# BMS_Interface.net
KiCad netlist of a schematic drawn in Altium Designer
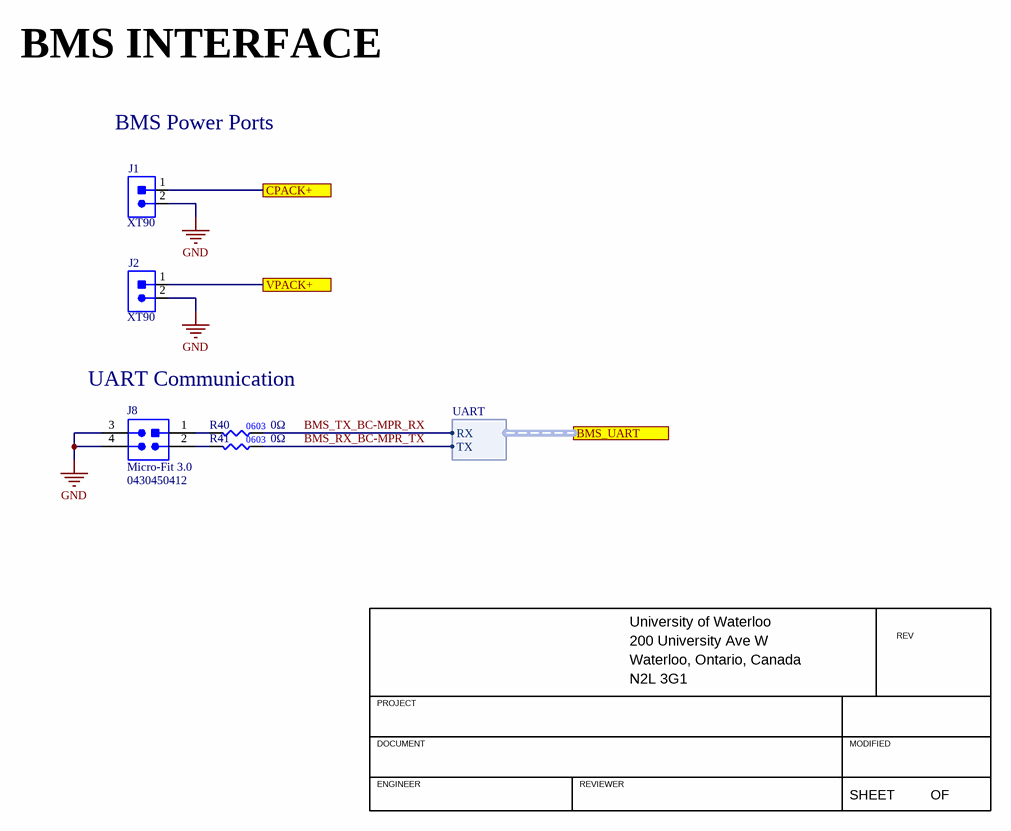
[diagram p0: BMS Interface.SchDoc]

(export (version "E")
  (design (tool "Eeschema 10.0.6"))
  (components
    (comp (ref "J1")
      (value "CON_2POS_XT90")
      (footprint "XT90")
      (description "HIGH QUALITY GOLD PLATED XT90 MA")
      (fields (field (name "PACKAGE/FOOTPRINT") "XT90"))
      (libsource (lib "Personal_Schematic_Library_2022") (part "CON_2POS_XT90"))
    )
    (comp (ref "J2")
      (value "CON_2POS_XT90")
      (footprint "XT90")
      (description "HIGH QUALITY GOLD PLATED XT90 MA")
      (fields (field (name "PACKAGE/FOOTPRINT") "XT90"))
      (libsource (lib "Personal_Schematic_Library_2022") (part "CON_2POS_XT90"))
    )
    (comp (ref "J8")
      (value "0430450412")
      (footprint "MOLEX-0430450412")
      (description "CONN HEADER VERT 4POS 3MM")
      (fields
        (field (name "FAMILY") "Micro-Fit 3.0")
        (field (name "MANUFACTURER PART NUMBER 1") "0430450412")
      )
      (libsource (lib "Personal_Schematic_Library_2022") (part "CON_MOLEX-HDR_2x2_TH"))
    )
    (comp (ref "R40")
      (value "0Ω")
      (footprint "RES0603")
      (description "RES 0 OHM JUMPER 1/10W 0603")
      (fields (field (name "Comment") "RES_0Ω_0603"))
      (libsource (lib "Personal_Schematic_Library_2022") (part "RES_0Ω_0603"))
    )
    (comp (ref "R41")
      (value "0Ω")
      (footprint "RES0603")
      (description "RES 0 OHM JUMPER 1/10W 0603")
      (fields (field (name "Comment") "RES_0Ω_0603"))
      (libsource (lib "Personal_Schematic_Library_2022") (part "RES_0Ω_0603"))
    )
  )
  (nets
    (net (code "2") (name "/BMS_RX_BC-MPR_TX") (class "Default")
      (node (ref "R41") (pin "2") (pinfunction "2_2") (pintype "passive"))
    )
    (net (code "3") (name "/BMS_TX_BC-MPR_RX") (class "Default")
      (node (ref "R40") (pin "2") (pinfunction "2_2") (pintype "passive"))
    )
    (net (code "4") (name "/CPACK+") (class "Default")
      (node (ref "J1") (pin "1") (pinfunction "1_1") (pintype "passive"))
    )
    (net (code "5") (name "/VPACK+") (class "Default")
      (node (ref "J2") (pin "1") (pinfunction "1_1") (pintype "passive"))
    )
    (net (code "7") (name "GND") (class "Default")
      (node (ref "J1") (pin "2") (pinfunction "2_2") (pintype "passive"))
      (node (ref "J2") (pin "2") (pinfunction "2_2") (pintype "passive"))
      (node (ref "J8") (pin "3") (pinfunction "3_3") (pintype "passive"))
      (node (ref "J8") (pin "4") (pinfunction "4_4") (pintype "passive"))
    )
    (net (code "8") (name "Net-(J8-Pad1)") (class "Default")
      (node (ref "J8") (pin "1") (pinfunction "1_1") (pintype "passive"))
      (node (ref "R40") (pin "1") (pinfunction "1_1") (pintype "passive"))
    )
    (net (code "9") (name "Net-(J8-Pad2)") (class "Default")
      (node (ref "J8") (pin "2") (pinfunction "2_2") (pintype "passive"))
      (node (ref "R41") (pin "1") (pinfunction "1_1") (pintype "passive"))
    )
  )
)
